# SCH_JingleTree_2025-12-07.net
KiCad netlist of a schematic drawn in EasyEDA
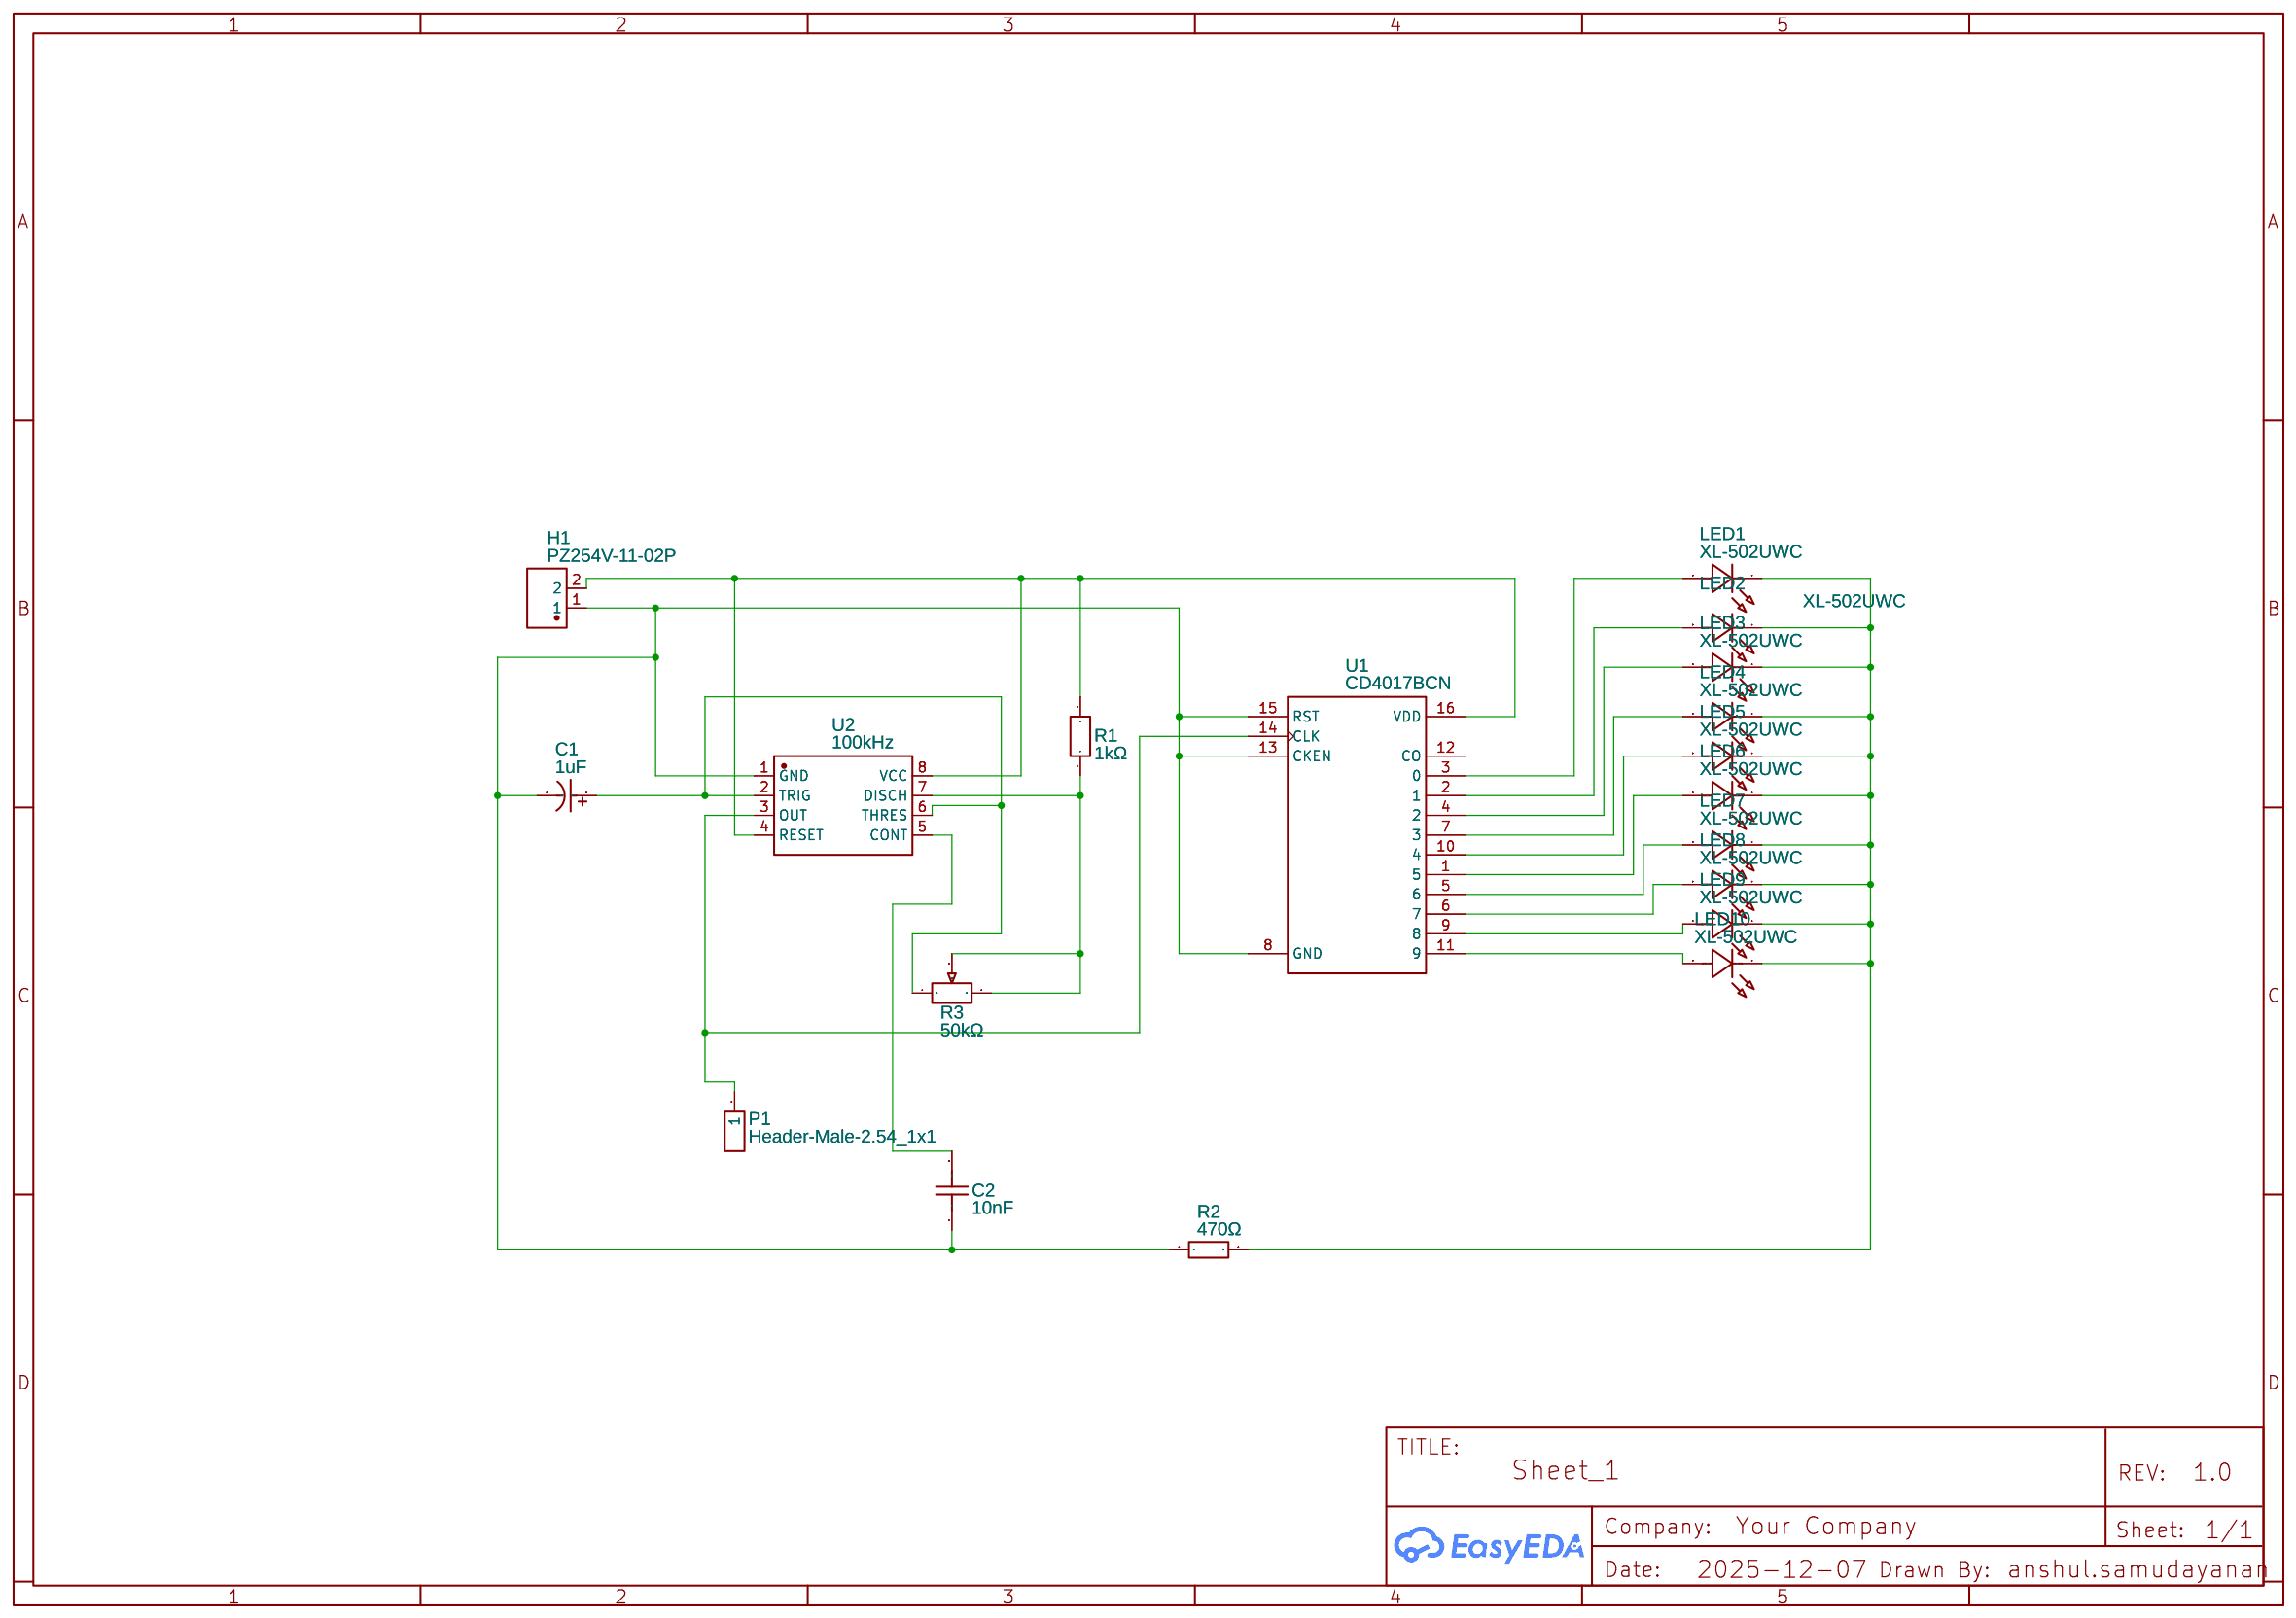
[diagram p0: schematic sheet]

(export (version "E")
  (design (tool "Eeschema 10.0.6"))
  (components
    (comp (ref "C1")
      (value "1uF")
      (fields (field (name "Manufacturer Part") "KF010M050C110A") (field (name "Manufacturer") "CapXon(丰宾)"))
      (libsource (lib "") (part "KF010M050C110A"))
    )
    (comp (ref "C2")
      (value "10nF")
      (fields (field (name "Manufacturer Part") "N09F1B103MN0B0S0N0") (field (name "Manufacturer") "STE(松田)"))
      (libsource (lib "") (part "N09F1B103MN0B0S0N0"))
    )
    (comp (ref "H1")
      (value "PZ254V-11-02P")
      (fields (field (name "Manufacturer") "XFCN(兴飞)"))
      (libsource (lib "") (part "PZ254V-11-02P"))
    )
    (comp (ref "LED1")
      (value "XL-502UWC")
      (fields (field (name "Manufacturer") "XINGLIGHT(成兴光)"))
      (libsource (lib "") (part "XL-502UWC"))
    )
    (comp (ref "LED2")
      (value "XL-502UWC")
      (fields (field (name "Manufacturer") "XINGLIGHT(成兴光)"))
      (libsource (lib "") (part "XL-502UWC"))
    )
    (comp (ref "LED3")
      (value "XL-502UWC")
      (fields (field (name "Manufacturer") "XINGLIGHT(成兴光)"))
      (libsource (lib "") (part "XL-502UWC"))
    )
    (comp (ref "LED4")
      (value "XL-502UWC")
      (fields (field (name "Manufacturer") "XINGLIGHT(成兴光)"))
      (libsource (lib "") (part "XL-502UWC"))
    )
    (comp (ref "LED5")
      (value "XL-502UWC")
      (fields (field (name "Manufacturer") "XINGLIGHT(成兴光)"))
      (libsource (lib "") (part "XL-502UWC"))
    )
    (comp (ref "LED6")
      (value "XL-502UWC")
      (fields (field (name "Manufacturer") "XINGLIGHT(成兴光)"))
      (libsource (lib "") (part "XL-502UWC"))
    )
    (comp (ref "LED7")
      (value "XL-502UWC")
      (fields (field (name "Manufacturer") "XINGLIGHT(成兴光)"))
      (libsource (lib "") (part "XL-502UWC"))
    )
    (comp (ref "LED8")
      (value "XL-502UWC")
      (fields (field (name "Manufacturer") "XINGLIGHT(成兴光)"))
      (libsource (lib "") (part "XL-502UWC"))
    )
    (comp (ref "LED9")
      (value "XL-502UWC")
      (fields (field (name "Manufacturer") "XINGLIGHT(成兴光)"))
      (libsource (lib "") (part "XL-502UWC"))
    )
    (comp (ref "LED10")
      (value "XL-502UWC")
      (fields (field (name "Manufacturer") "XINGLIGHT(成兴光)"))
      (libsource (lib "") (part "XL-502UWC"))
    )
    (comp (ref "P1")
      (value "Header-Male-2.54_1x1")
      (fields (field (name "Manufacturer Part") "2.54-1*1P针") (field (name "Manufacturer") "BOOMELE(博穆精密)"))
      (libsource (lib "") (part "Header-Male-2.54_1x1"))
    )
    (comp (ref "R1")
      (value "1kΩ")
      (fields (field (name "Manufacturer Part") "MF1/4W-1KΩ±1%T52") (field (name "Manufacturer") "华星机电"))
      (libsource (lib "") (part "MF1/4W-1KΩ±1%T52"))
    )
    (comp (ref "R2")
      (value "470Ω")
      (fields
        (field (name "Manufacturer Part") "MFR0W4F4700A50")
        (field (name "Manufacturer") "UNI-ROYAL(厚声)")
      )
      (libsource (lib "") (part "MFR0W4F4700A50"))
    )
    (comp (ref "R3")
      (value "50kΩ")
      (fields (field (name "Manufacturer Part") "3296X-1-503") (field (name "Manufacturer") "BOCHEN(博晨)"))
      (libsource (lib "") (part "3296X-1-503_C118912"))
    )
    (comp (ref "U1") (value "CD4017BCN") (libsource (lib "") (part "CD4017BCN")))
    (comp (ref "U2")
      (value "100kHz")
      (fields (field (name "Manufacturer Part") "NE555P") (field (name "Manufacturer") "TI(德州仪器)"))
      (libsource (lib "") (part "NE555P"))
    )
  )
  (nets
    (net (code "1") (name "Net-(LED1-A)") (class "Default")
      (node (ref "LED1") (pin "2") (pinfunction "A_2") (pintype "unspecified"))
      (node (ref "U1") (pin "3") (pinfunction "0_3") (pintype "output"))
    )
    (net (code "2") (name "Net-(LED1-K)") (class "Default")
      (node (ref "LED1") (pin "1") (pinfunction "K_1") (pintype "unspecified"))
      (node (ref "LED10") (pin "1") (pinfunction "K_1") (pintype "unspecified"))
      (node (ref "LED2") (pin "1") (pinfunction "K_1") (pintype "unspecified"))
      (node (ref "LED3") (pin "1") (pinfunction "K_1") (pintype "unspecified"))
      (node (ref "LED4") (pin "1") (pinfunction "K_1") (pintype "unspecified"))
      (node (ref "LED5") (pin "1") (pinfunction "K_1") (pintype "unspecified"))
      (node (ref "LED6") (pin "1") (pinfunction "K_1") (pintype "unspecified"))
      (node (ref "LED7") (pin "1") (pinfunction "K_1") (pintype "unspecified"))
      (node (ref "LED8") (pin "1") (pinfunction "K_1") (pintype "unspecified"))
      (node (ref "LED9") (pin "1") (pinfunction "K_1") (pintype "unspecified"))
      (node (ref "R2") (pin "2") (pinfunction "2_2") (pintype "input"))
    )
    (net (code "3") (name "Net-(LED2-A)") (class "Default")
      (node (ref "LED2") (pin "2") (pinfunction "A_2") (pintype "unspecified"))
      (node (ref "U1") (pin "2") (pinfunction "1_2") (pintype "output"))
    )
    (net (code "4") (name "Net-(LED3-A)") (class "Default")
      (node (ref "LED3") (pin "2") (pinfunction "A_2") (pintype "unspecified"))
      (node (ref "U1") (pin "4") (pinfunction "2_4") (pintype "output"))
    )
    (net (code "5") (name "Net-(LED4-A)") (class "Default")
      (node (ref "LED4") (pin "2") (pinfunction "A_2") (pintype "unspecified"))
      (node (ref "U1") (pin "7") (pinfunction "3_7") (pintype "output"))
    )
    (net (code "6") (name "Net-(LED5-A)") (class "Default")
      (node (ref "LED5") (pin "2") (pinfunction "A_2") (pintype "unspecified"))
      (node (ref "U1") (pin "10") (pinfunction "4_10") (pintype "output"))
    )
    (net (code "7") (name "Net-(LED6-A)") (class "Default")
      (node (ref "LED6") (pin "2") (pinfunction "A_2") (pintype "unspecified"))
      (node (ref "U1") (pin "1") (pinfunction "5_1") (pintype "output"))
    )
    (net (code "8") (name "Net-(LED7-A)") (class "Default")
      (node (ref "LED7") (pin "2") (pinfunction "A_2") (pintype "unspecified"))
      (node (ref "U1") (pin "5") (pinfunction "6_5") (pintype "output"))
    )
    (net (code "9") (name "Net-(LED8-A)") (class "Default")
      (node (ref "LED8") (pin "2") (pinfunction "A_2") (pintype "unspecified"))
      (node (ref "U1") (pin "6") (pinfunction "7_6") (pintype "output"))
    )
    (net (code "10") (name "Net-(LED9-A)") (class "Default")
      (node (ref "LED9") (pin "2") (pinfunction "A_2") (pintype "unspecified"))
      (node (ref "U1") (pin "9") (pinfunction "8_9") (pintype "output"))
    )
    (net (code "11") (name "Net-(LED10-A)") (class "Default")
      (node (ref "LED10") (pin "2") (pinfunction "A_2") (pintype "unspecified"))
      (node (ref "U1") (pin "11") (pinfunction "9_11") (pintype "output"))
    )
    (net (code "12") (name "Net-(U1-CKEN)") (class "Default")
      (node (ref "C1") (pin "2") (pinfunction "2_2") (pintype "input"))
      (node (ref "C2") (pin "1") (pinfunction "1_1") (pintype "unspecified"))
      (node (ref "H1") (pin "1") (pinfunction "1_1") (pintype "unspecified"))
      (node (ref "R2") (pin "1") (pinfunction "1_1") (pintype "input"))
      (node (ref "U1") (pin "13") (pinfunction "CKEN_13") (pintype "unspecified"))
      (node (ref "U1") (pin "15") (pinfunction "RST_15") (pintype "unspecified"))
      (node (ref "U1") (pin "8") (pinfunction "GND_8") (pintype "passive"))
      (node (ref "U2") (pin "1") (pinfunction "GND_1") (pintype "unspecified"))
    )
    (net (code "13") (name "Net-(U1-CLK)") (class "Default")
      (node (ref "P1") (pin "1") (pinfunction "1_1") (pintype "input"))
      (node (ref "U1") (pin "14") (pinfunction "CLK_14") (pintype "unspecified"))
      (node (ref "U2") (pin "3") (pinfunction "OUT_3") (pintype "unspecified"))
    )
    (net (code "14") (name "Net-(U1-VDD)") (class "Default")
      (node (ref "H1") (pin "2") (pinfunction "2_2") (pintype "unspecified"))
      (node (ref "R1") (pin "2") (pinfunction "2_2") (pintype "unspecified"))
      (node (ref "U1") (pin "16") (pinfunction "VDD_16") (pintype "passive"))
      (node (ref "U2") (pin "4") (pinfunction "RESET_4") (pintype "unspecified"))
      (node (ref "U2") (pin "8") (pinfunction "VCC_8") (pintype "unspecified"))
    )
    (net (code "15") (name "Net-(U2-CONT)") (class "Default")
      (node (ref "C2") (pin "2") (pinfunction "2_2") (pintype "unspecified"))
      (node (ref "U2") (pin "5") (pinfunction "CONT_5") (pintype "unspecified"))
    )
    (net (code "16") (name "Net-(U2-DISCH)") (class "Default")
      (node (ref "R1") (pin "1") (pinfunction "1_1") (pintype "unspecified"))
      (node (ref "R3") (pin "2") (pinfunction "2_2") (pintype "input"))
      (node (ref "R3") (pin "3") (pinfunction "3_3") (pintype "input"))
      (node (ref "U2") (pin "7") (pinfunction "DISCH_7") (pintype "unspecified"))
    )
    (net (code "17") (name "Net-(U2-THRES)") (class "Default")
      (node (ref "C1") (pin "1") (pinfunction "1_1") (pintype "input"))
      (node (ref "R3") (pin "1") (pinfunction "1_1") (pintype "input"))
      (node (ref "U2") (pin "2") (pinfunction "TRIG_2") (pintype "unspecified"))
      (node (ref "U2") (pin "6") (pinfunction "THRES_6") (pintype "unspecified"))
    )
    (net (code "18") (name "unconnected-(U1-CO-Pad12)") (class "Default")
      (node (ref "U1") (pin "12") (pinfunction "CO_12") (pintype "output"))
    )
  )
)
